# ce3_redraw.net
KiCad netlist of a schematic drawn in EAGLE
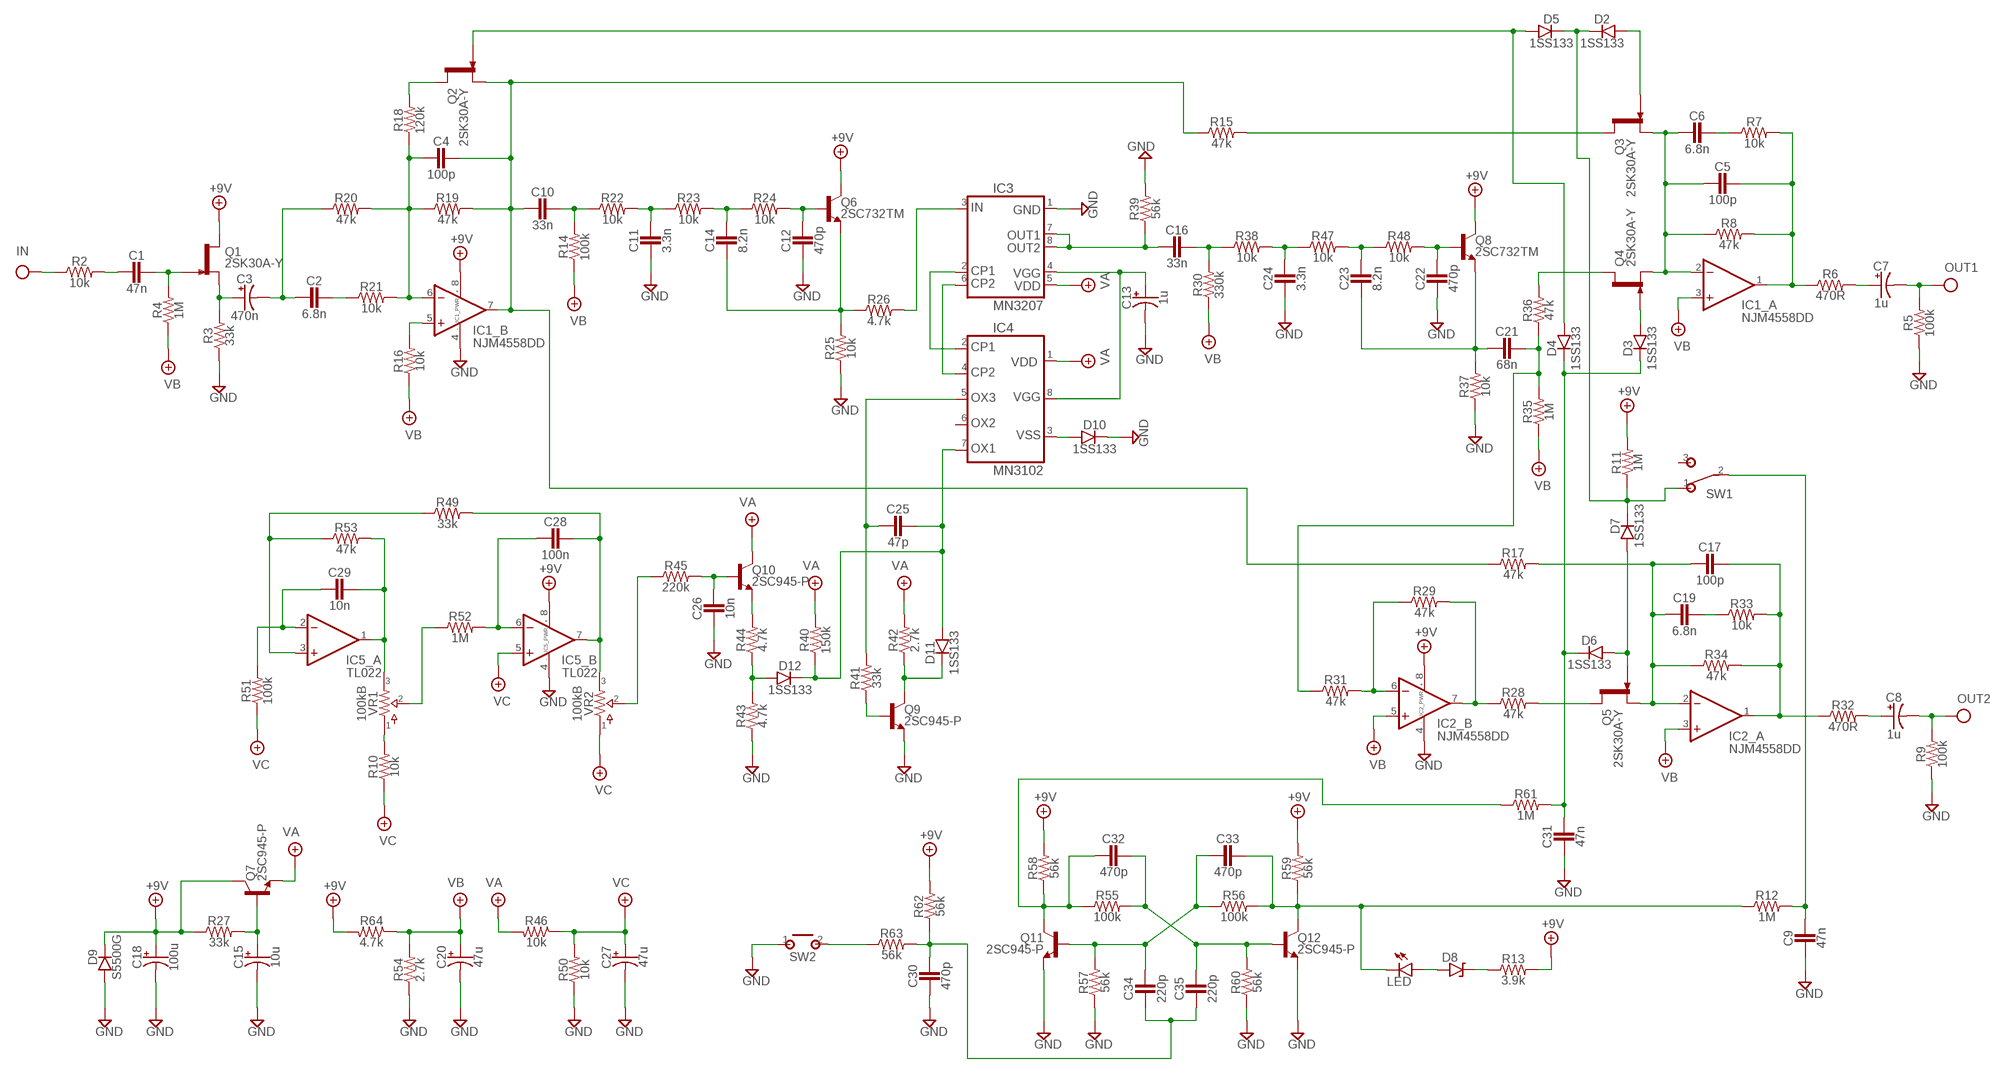
[diagram p0: schematic, sheet 1]

(export (version "E")
  (design (tool "Eeschema 10.0.6"))
  (components
    (comp (ref "C1")
      (value "47n")
      (footprint "eagle-import:BOX_SMALL")
      (libsource (lib "eagle-import") (part "CER/FILMBOX.1"))
    )
    (comp (ref "C2")
      (value "6.8n")
      (footprint "eagle-import:BOX_SMALL")
      (libsource (lib "eagle-import") (part "CER/FILMBOX.1"))
    )
    (comp (ref "C3")
      (value "470n")
      (footprint "eagle-import:040_020")
      (libsource (lib "eagle-import") (part "0400"))
    )
    (comp (ref "C4")
      (value "100p")
      (footprint "eagle-import:BOX_SMALL")
      (libsource (lib "eagle-import") (part "CER/FILMBOX.1"))
    )
    (comp (ref "C5")
      (value "100p")
      (footprint "eagle-import:BOX_SMALL")
      (libsource (lib "eagle-import") (part "CER/FILMBOX.1"))
    )
    (comp (ref "C6")
      (value "6.8n")
      (footprint "eagle-import:BOX_SMALL")
      (libsource (lib "eagle-import") (part "CER/FILMBOX.1"))
    )
    (comp (ref "C7")
      (value "1u")
      (footprint "eagle-import:040_020")
      (libsource (lib "eagle-import") (part "0400"))
    )
    (comp (ref "C8")
      (value "1u")
      (footprint "eagle-import:040_020")
      (libsource (lib "eagle-import") (part "0400"))
    )
    (comp (ref "C9")
      (value "47n")
      (footprint "eagle-import:BOX_SMALL")
      (libsource (lib "eagle-import") (part "CER/FILMBOX.1"))
    )
    (comp (ref "C10")
      (value "33n")
      (footprint "eagle-import:BOX_SMALL")
      (libsource (lib "eagle-import") (part "CER/FILMBOX.1"))
    )
    (comp (ref "C11")
      (value "3.3n")
      (footprint "eagle-import:BOX_SMALL")
      (libsource (lib "eagle-import") (part "CER/FILMBOX.1"))
    )
    (comp (ref "C12")
      (value "470p")
      (footprint "eagle-import:BOX_SMALL")
      (libsource (lib "eagle-import") (part "CER/FILMBOX.1"))
    )
    (comp (ref "C13")
      (value "1u")
      (footprint "eagle-import:040_020")
      (libsource (lib "eagle-import") (part "0400"))
    )
    (comp (ref "C14")
      (value "8.2n")
      (footprint "eagle-import:BOX_SMALL")
      (libsource (lib "eagle-import") (part "CER/FILMBOX.1"))
    )
    (comp (ref "C15")
      (value "10u")
      (footprint "eagle-import:040_020")
      (libsource (lib "eagle-import") (part "0400"))
    )
    (comp (ref "C16")
      (value "33n")
      (footprint "eagle-import:BOX_SMALL")
      (libsource (lib "eagle-import") (part "CER/FILMBOX.1"))
    )
    (comp (ref "C17")
      (value "100p")
      (footprint "eagle-import:BOX_SMALL")
      (libsource (lib "eagle-import") (part "CER/FILMBOX.1"))
    )
    (comp (ref "C18")
      (value "100u")
      (footprint "eagle-import:040_020")
      (libsource (lib "eagle-import") (part "0400"))
    )
    (comp (ref "C19")
      (value "6.8n")
      (footprint "eagle-import:BOX_SMALL")
      (libsource (lib "eagle-import") (part "CER/FILMBOX.1"))
    )
    (comp (ref "C20")
      (value "47u")
      (footprint "eagle-import:040_020")
      (libsource (lib "eagle-import") (part "0400"))
    )
    (comp (ref "C21")
      (value "68n")
      (footprint "eagle-import:BOX_SMALL")
      (libsource (lib "eagle-import") (part "CER/FILMBOX.1"))
    )
    (comp (ref "C22")
      (value "470p")
      (footprint "eagle-import:BOX_SMALL")
      (libsource (lib "eagle-import") (part "CER/FILMBOX.1"))
    )
    (comp (ref "C23")
      (value "8.2n")
      (footprint "eagle-import:BOX_SMALL")
      (libsource (lib "eagle-import") (part "CER/FILMBOX.1"))
    )
    (comp (ref "C24")
      (value "3.3n")
      (footprint "eagle-import:BOX_SMALL")
      (libsource (lib "eagle-import") (part "CER/FILMBOX.1"))
    )
    (comp (ref "C25")
      (value "47p")
      (footprint "eagle-import:BOX_SMALL")
      (libsource (lib "eagle-import") (part "CER/FILMBOX.1"))
    )
    (comp (ref "C26")
      (value "10n")
      (footprint "eagle-import:BOX_SMALL")
      (libsource (lib "eagle-import") (part "CER/FILMBOX.1"))
    )
    (comp (ref "C27")
      (value "47u")
      (footprint "eagle-import:040_020")
      (libsource (lib "eagle-import") (part "0400"))
    )
    (comp (ref "C28")
      (value "100n")
      (footprint "eagle-import:BOX_SMALL")
      (libsource (lib "eagle-import") (part "CER/FILMBOX.1"))
    )
    (comp (ref "C29")
      (value "10n")
      (footprint "eagle-import:BOX_SMALL")
      (libsource (lib "eagle-import") (part "CER/FILMBOX.1"))
    )
    (comp (ref "C30")
      (value "470p")
      (footprint "eagle-import:BOX_SMALL")
      (libsource (lib "eagle-import") (part "CER/FILMBOX.1"))
    )
    (comp (ref "C31")
      (value "47n")
      (footprint "eagle-import:BOX_SMALL")
      (libsource (lib "eagle-import") (part "CER/FILMBOX.1"))
    )
    (comp (ref "C32")
      (value "470p")
      (footprint "eagle-import:BOX_SMALL")
      (libsource (lib "eagle-import") (part "CER/FILMBOX.1"))
    )
    (comp (ref "C33")
      (value "470p")
      (footprint "eagle-import:BOX_SMALL")
      (libsource (lib "eagle-import") (part "CER/FILMBOX.1"))
    )
    (comp (ref "C34")
      (value "220p")
      (footprint "eagle-import:BOX_SMALL")
      (libsource (lib "eagle-import") (part "CER/FILMBOX.1"))
    )
    (comp (ref "C35")
      (value "220p")
      (footprint "eagle-import:BOX_SMALL")
      (libsource (lib "eagle-import") (part "CER/FILMBOX.1"))
    )
    (comp (ref "D2")
      (value "1SS133")
      (footprint "eagle-import:DO35-2")
      (libsource (lib "eagle-import") (part "DO35.2"))
    )
    (comp (ref "D3")
      (value "1SS133")
      (footprint "eagle-import:DO35-2")
      (libsource (lib "eagle-import") (part "DO35.2"))
    )
    (comp (ref "D4")
      (value "1SS133")
      (footprint "eagle-import:DO35-2")
      (libsource (lib "eagle-import") (part "DO35.2"))
    )
    (comp (ref "D5")
      (value "1SS133")
      (footprint "eagle-import:DO35-2")
      (libsource (lib "eagle-import") (part "DO35.2"))
    )
    (comp (ref "D6")
      (value "1SS133")
      (footprint "eagle-import:DO35-2")
      (libsource (lib "eagle-import") (part "DO35.2"))
    )
    (comp (ref "D7")
      (value "1SS133")
      (footprint "eagle-import:DO35-2")
      (libsource (lib "eagle-import") (part "DO35.2"))
    )
    (comp (ref "D8")
      (value "ZENER.2")
      (footprint "eagle-import:DO41-2")
      (libsource (lib "eagle-import") (part "ZENER.2"))
    )
    (comp (ref "D9")
      (value "S5500G")
      (footprint "eagle-import:DO35-2")
      (libsource (lib "eagle-import") (part "DO35.2"))
    )
    (comp (ref "D10")
      (value "1SS133")
      (footprint "eagle-import:DO35-2")
      (libsource (lib "eagle-import") (part "DO35.2"))
    )
    (comp (ref "D11")
      (value "1SS133")
      (footprint "eagle-import:DO35-2")
      (libsource (lib "eagle-import") (part "DO35.2"))
    )
    (comp (ref "D12")
      (value "1SS133")
      (footprint "eagle-import:DO35-2")
      (libsource (lib "eagle-import") (part "DO35.2"))
    )
    (comp (ref "IC1")
      (value "NJM4558DD")
      (footprint "eagle-import:DIL0")
      (libsource (lib "eagle-import") (part "DUALTH"))
    )
    (comp (ref "IC2")
      (value "NJM4558DD")
      (footprint "eagle-import:DIL0")
      (libsource (lib "eagle-import") (part "DUALTH"))
    )
    (comp (ref "IC3")
      (value "MN3207")
      (footprint "eagle-import:DIL0")
      (libsource (lib "eagle-import") (part "BL3208"))
    )
    (comp (ref "IC4")
      (value "MN3102")
      (footprint "eagle-import:DIL8")
      (libsource (lib "eagle-import") (part "CLOCK"))
    )
    (comp (ref "IC5")
      (value "TL022")
      (footprint "eagle-import:DIL0")
      (libsource (lib "eagle-import") (part "DUALTH"))
    )
    (comp (ref "LED")
      (value "LED")
      (footprint "eagle-import:3MM_D")
      (libsource (lib "eagle-import") (part "LED"))
    )
    (comp (ref "Q1")
      (value "2SK30A-Y")
      (footprint "eagle-import:TO92-")
      (libsource (lib "eagle-import") (part "2N5457"))
    )
    (comp (ref "Q2")
      (value "2SK30A-Y")
      (footprint "eagle-import:TO92-")
      (libsource (lib "eagle-import") (part "2N5457"))
    )
    (comp (ref "Q3")
      (value "2SK30A-Y")
      (footprint "eagle-import:TO92-")
      (libsource (lib "eagle-import") (part "2N5457"))
    )
    (comp (ref "Q4")
      (value "2SK30A-Y")
      (footprint "eagle-import:TO92-")
      (libsource (lib "eagle-import") (part "2N5457"))
    )
    (comp (ref "Q5")
      (value "2SK30A-Y")
      (footprint "eagle-import:TO92-")
      (libsource (lib "eagle-import") (part "2N5457"))
    )
    (comp (ref "Q6")
      (value "2SC732TM")
      (footprint "eagle-import:TO92-")
      (libsource (lib "eagle-import") (part "2SC828A"))
    )
    (comp (ref "Q7")
      (value "2SC945-P")
      (footprint "eagle-import:TO92-")
      (libsource (lib "eagle-import") (part "2SC828A"))
    )
    (comp (ref "Q8")
      (value "2SC732TM")
      (footprint "eagle-import:TO92-")
      (libsource (lib "eagle-import") (part "2SC828A"))
    )
    (comp (ref "Q9")
      (value "2SC945-P")
      (footprint "eagle-import:TO92-")
      (libsource (lib "eagle-import") (part "2SC828A"))
    )
    (comp (ref "Q10")
      (value "2SC945-P")
      (footprint "eagle-import:TO92-")
      (libsource (lib "eagle-import") (part "2SC828A"))
    )
    (comp (ref "Q11")
      (value "2SC945-P")
      (footprint "eagle-import:TO92-")
      (libsource (lib "eagle-import") (part "2SC828A"))
    )
    (comp (ref "Q12")
      (value "2SC945-P")
      (footprint "eagle-import:TO92-")
      (libsource (lib "eagle-import") (part "2SC828A"))
    )
    (comp (ref "R2")
      (value "10k")
      (footprint "eagle-import:R0207_3")
      (libsource (lib "eagle-import") (part "R_.3B"))
    )
    (comp (ref "R3")
      (value "33k")
      (footprint "eagle-import:R0207_3")
      (libsource (lib "eagle-import") (part "R_.3B"))
    )
    (comp (ref "R4")
      (value "1M")
      (footprint "eagle-import:R0207_3")
      (libsource (lib "eagle-import") (part "R_.3B"))
    )
    (comp (ref "R5")
      (value "100k")
      (footprint "eagle-import:R0207_3")
      (libsource (lib "eagle-import") (part "R_.3B"))
    )
    (comp (ref "R6")
      (value "470R")
      (footprint "eagle-import:R0207_3")
      (libsource (lib "eagle-import") (part "R_.3B"))
    )
    (comp (ref "R7")
      (value "10k")
      (footprint "eagle-import:R0207_3")
      (libsource (lib "eagle-import") (part "R_.3B"))
    )
    (comp (ref "R8")
      (value "47k")
      (footprint "eagle-import:R0207_3")
      (libsource (lib "eagle-import") (part "R_.3B"))
    )
    (comp (ref "R9")
      (value "100k")
      (footprint "eagle-import:R0207_3")
      (libsource (lib "eagle-import") (part "R_.3B"))
    )
    (comp (ref "R10")
      (value "10k")
      (footprint "eagle-import:R0207_3")
      (libsource (lib "eagle-import") (part "R_.3B"))
    )
    (comp (ref "R11")
      (value "1M")
      (footprint "eagle-import:R0207_3")
      (libsource (lib "eagle-import") (part "R_.3B"))
    )
    (comp (ref "R12")
      (value "1M")
      (footprint "eagle-import:R0207_3")
      (libsource (lib "eagle-import") (part "R_.3B"))
    )
    (comp (ref "R13")
      (value "3.9k")
      (footprint "eagle-import:R0207_3")
      (libsource (lib "eagle-import") (part "R_.3B"))
    )
    (comp (ref "R14")
      (value "100k")
      (footprint "eagle-import:R0207_3")
      (libsource (lib "eagle-import") (part "R_.3B"))
    )
    (comp (ref "R15")
      (value "47k")
      (footprint "eagle-import:R0207_3")
      (libsource (lib "eagle-import") (part "R_.3B"))
    )
    (comp (ref "R16")
      (value "10k")
      (footprint "eagle-import:R0207_3")
      (libsource (lib "eagle-import") (part "R_.3B"))
    )
    (comp (ref "R17")
      (value "47k")
      (footprint "eagle-import:R0207_3")
      (libsource (lib "eagle-import") (part "R_.3B"))
    )
    (comp (ref "R18")
      (value "120k")
      (footprint "eagle-import:R0207_3")
      (libsource (lib "eagle-import") (part "R_.3B"))
    )
    (comp (ref "R19")
      (value "47k")
      (footprint "eagle-import:R0207_3")
      (libsource (lib "eagle-import") (part "R_.3B"))
    )
    (comp (ref "R20")
      (value "47k")
      (footprint "eagle-import:R0207_3")
      (libsource (lib "eagle-import") (part "R_.3B"))
    )
    (comp (ref "R21")
      (value "10k")
      (footprint "eagle-import:R0207_3")
      (libsource (lib "eagle-import") (part "R_.3B"))
    )
    (comp (ref "R22")
      (value "10k")
      (footprint "eagle-import:R0207_3")
      (libsource (lib "eagle-import") (part "R_.3B"))
    )
    (comp (ref "R23")
      (value "10k")
      (footprint "eagle-import:R0207_3")
      (libsource (lib "eagle-import") (part "R_.3B"))
    )
    (comp (ref "R24")
      (value "10k")
      (footprint "eagle-import:R0207_3")
      (libsource (lib "eagle-import") (part "R_.3B"))
    )
    (comp (ref "R25")
      (value "10k")
      (footprint "eagle-import:R0207_3")
      (libsource (lib "eagle-import") (part "R_.3B"))
    )
    (comp (ref "R26")
      (value "4.7k")
      (footprint "eagle-import:R0207_3")
      (libsource (lib "eagle-import") (part "R_.3B"))
    )
    (comp (ref "R27")
      (value "33k")
      (footprint "eagle-import:R0207_3")
      (libsource (lib "eagle-import") (part "R_.3B"))
    )
    (comp (ref "R28")
      (value "47k")
      (footprint "eagle-import:R0207_3")
      (libsource (lib "eagle-import") (part "R_.3B"))
    )
    (comp (ref "R29")
      (value "47k")
      (footprint "eagle-import:R0207_3")
      (libsource (lib "eagle-import") (part "R_.3B"))
    )
    (comp (ref "R30")
      (value "330k")
      (footprint "eagle-import:R0207_3")
      (libsource (lib "eagle-import") (part "R_.3B"))
    )
    (comp (ref "R31")
      (value "47k")
      (footprint "eagle-import:R0207_3")
      (libsource (lib "eagle-import") (part "R_.3B"))
    )
    (comp (ref "R32")
      (value "470R")
      (footprint "eagle-import:R0207_3")
      (libsource (lib "eagle-import") (part "R_.3B"))
    )
    (comp (ref "R33")
      (value "10k")
      (footprint "eagle-import:R0207_3")
      (libsource (lib "eagle-import") (part "R_.3B"))
    )
    (comp (ref "R34")
      (value "47k")
      (footprint "eagle-import:R0207_3")
      (libsource (lib "eagle-import") (part "R_.3B"))
    )
    (comp (ref "R35")
      (value "1M")
      (footprint "eagle-import:R0207_3")
      (libsource (lib "eagle-import") (part "R_.3B"))
    )
    (comp (ref "R36")
      (value "47k")
      (footprint "eagle-import:R0207_3")
      (libsource (lib "eagle-import") (part "R_.3B"))
    )
    (comp (ref "R37")
      (value "10k")
      (footprint "eagle-import:R0207_3")
      (libsource (lib "eagle-import") (part "R_.3B"))
    )
    (comp (ref "R38")
      (value "10k")
      (footprint "eagle-import:R0207_3")
      (libsource (lib "eagle-import") (part "R_.3B"))
    )
    (comp (ref "R39")
      (value "56k")
      (footprint "eagle-import:R0207_3")
      (libsource (lib "eagle-import") (part "R_.3B"))
    )
    (comp (ref "R40")
      (value "150k")
      (footprint "eagle-import:R0207_3")
      (libsource (lib "eagle-import") (part "R_.3B"))
    )
    (comp (ref "R41")
      (value "33k")
      (footprint "eagle-import:R0207_3")
      (libsource (lib "eagle-import") (part "R_.3B"))
    )
    (comp (ref "R42")
      (value "2.7k")
      (footprint "eagle-import:R0207_3")
      (libsource (lib "eagle-import") (part "R_.3B"))
    )
    (comp (ref "R43")
      (value "4.7k")
      (footprint "eagle-import:R0207_3")
      (libsource (lib "eagle-import") (part "R_.3B"))
    )
    (comp (ref "R44")
      (value "4.7k")
      (footprint "eagle-import:R0207_3")
      (libsource (lib "eagle-import") (part "R_.3B"))
    )
    (comp (ref "R45")
      (value "220k")
      (footprint "eagle-import:R0207_3")
      (libsource (lib "eagle-import") (part "R_.3B"))
    )
    (comp (ref "R46")
      (value "10k")
      (footprint "eagle-import:R0207_3")
      (libsource (lib "eagle-import") (part "R_.3B"))
    )
    (comp (ref "R47")
      (value "10k")
      (footprint "eagle-import:R0207_3")
      (libsource (lib "eagle-import") (part "R_.3B"))
    )
    (comp (ref "R48")
      (value "10k")
      (footprint "eagle-import:R0207_3")
      (libsource (lib "eagle-import") (part "R_.3B"))
    )
    (comp (ref "R49")
      (value "33k")
      (footprint "eagle-import:R0207_3")
      (libsource (lib "eagle-import") (part "R_.3B"))
    )
    (comp (ref "R50")
      (value "10k")
      (footprint "eagle-import:R0207_3")
      (libsource (lib "eagle-import") (part "R_.3B"))
    )
    (comp (ref "R51")
      (value "100k")
      (footprint "eagle-import:R0207_3")
      (libsource (lib "eagle-import") (part "R_.3B"))
    )
    (comp (ref "R52")
      (value "1M")
      (footprint "eagle-import:R0207_3")
      (libsource (lib "eagle-import") (part "R_.3B"))
    )
    (comp (ref "R53")
      (value "47k")
      (footprint "eagle-import:R0207_3")
      (libsource (lib "eagle-import") (part "R_.3B"))
    )
    (comp (ref "R54")
      (value "2.7k")
      (footprint "eagle-import:R0207_3")
      (libsource (lib "eagle-import") (part "R_.3B"))
    )
    (comp (ref "R55")
      (value "100k")
      (footprint "eagle-import:R0207_3")
      (libsource (lib "eagle-import") (part "R_.3B"))
    )
    (comp (ref "R56")
      (value "100k")
      (footprint "eagle-import:R0207_3")
      (libsource (lib "eagle-import") (part "R_.3B"))
    )
    (comp (ref "R57")
      (value "56k")
      (footprint "eagle-import:R0207_3")
      (libsource (lib "eagle-import") (part "R_.3B"))
    )
    (comp (ref "R58")
      (value "56k")
      (footprint "eagle-import:R0207_3")
      (libsource (lib "eagle-import") (part "R_.3B"))
    )
    (comp (ref "R59")
      (value "56k")
      (footprint "eagle-import:R0207_3")
      (libsource (lib "eagle-import") (part "R_.3B"))
    )
    (comp (ref "R60")
      (value "56k")
      (footprint "eagle-import:R0207_3")
      (libsource (lib "eagle-import") (part "R_.3B"))
    )
    (comp (ref "R61")
      (value "1M")
      (footprint "eagle-import:R0207_3")
      (libsource (lib "eagle-import") (part "R_.3B"))
    )
    (comp (ref "R62")
      (value "56k")
      (footprint "eagle-import:R0207_3")
      (libsource (lib "eagle-import") (part "R_.3B"))
    )
    (comp (ref "R63")
      (value "56k")
      (footprint "eagle-import:R0207_3")
      (libsource (lib "eagle-import") (part "R_.3B"))
    )
    (comp (ref "R64")
      (value "4.7k")
      (footprint "eagle-import:R0207_3")
      (libsource (lib "eagle-import") (part "R_.3B"))
    )
    (comp (ref "SW1")
      (value "SPDT")
      (footprint "eagle-import:M9040P")
      (libsource (lib "eagle-import") (part "SPDT"))
    )
    (comp (ref "SW2")
      (value "MOMENTARY")
      (footprint "eagle-import:SPST")
      (libsource (lib "eagle-import") (part "MOMENTARY"))
    )
    (comp (ref "VR1")
      (value "100kB")
      (footprint "eagle-import:16MM")
      (libsource (lib "eagle-import") (part "POTS16MM"))
    )
    (comp (ref "VR2")
      (value "100kB")
      (footprint "eagle-import:16MM")
      (libsource (lib "eagle-import") (part "POTS16MM"))
    )
  )
  (nets
    (net (code "1") (name "+9V") (class "Default")
      (node (ref "C18") (pin "+") (pinfunction "+_+") (pintype "passive"))
      (node (ref "D9") (pin "C") (pinfunction "C_C") (pintype "passive"))
      (node (ref "IC1") (pin "8") (pinfunction "V+_8") (pintype "power_in"))
      (node (ref "IC2") (pin "8") (pinfunction "V+_8") (pintype "power_in"))
      (node (ref "IC5") (pin "8") (pinfunction "V+_8") (pintype "power_in"))
      (node (ref "Q1") (pin "3") (pinfunction "D_3") (pintype "passive"))
      (node (ref "Q6") (pin "2") (pinfunction "C_2") (pintype "passive"))
      (node (ref "Q7") (pin "2") (pinfunction "C_2") (pintype "passive"))
      (node (ref "Q8") (pin "2") (pinfunction "C_2") (pintype "passive"))
      (node (ref "R11") (pin "2") (pinfunction "2_2") (pintype "passive"))
      (node (ref "R13") (pin "2") (pinfunction "2_2") (pintype "passive"))
      (node (ref "R27") (pin "1") (pinfunction "1_1") (pintype "passive"))
      (node (ref "R58") (pin "2") (pinfunction "2_2") (pintype "passive"))
      (node (ref "R59") (pin "2") (pinfunction "2_2") (pintype "passive"))
      (node (ref "R62") (pin "2") (pinfunction "2_2") (pintype "passive"))
      (node (ref "R64") (pin "2") (pinfunction "2_2") (pintype "passive"))
    )
    (net (code "2") (name "GND") (class "Default")
      (node (ref "C11") (pin "2") (pinfunction "2_2") (pintype "passive"))
      (node (ref "C12") (pin "2") (pinfunction "2_2") (pintype "passive"))
      (node (ref "C13") (pin "-") (pinfunction "-_-") (pintype "passive"))
      (node (ref "C15") (pin "-") (pinfunction "-_-") (pintype "passive"))
      (node (ref "C18") (pin "-") (pinfunction "-_-") (pintype "passive"))
      (node (ref "C20") (pin "-") (pinfunction "-_-") (pintype "passive"))
      (node (ref "C22") (pin "2") (pinfunction "2_2") (pintype "passive"))
      (node (ref "C24") (pin "2") (pinfunction "2_2") (pintype "passive"))
      (node (ref "C26") (pin "2") (pinfunction "2_2") (pintype "passive"))
      (node (ref "C27") (pin "-") (pinfunction "-_-") (pintype "passive"))
      (node (ref "C30") (pin "2") (pinfunction "2_2") (pintype "passive"))
      (node (ref "C31") (pin "2") (pinfunction "2_2") (pintype "passive"))
      (node (ref "C9") (pin "2") (pinfunction "2_2") (pintype "passive"))
      (node (ref "D10") (pin "C") (pinfunction "C_C") (pintype "passive"))
      (node (ref "D9") (pin "A") (pinfunction "A_A") (pintype "passive"))
      (node (ref "IC1") (pin "4") (pinfunction "V-_4") (pintype "power_in"))
      (node (ref "IC2") (pin "4") (pinfunction "V-_4") (pintype "power_in"))
      (node (ref "IC3") (pin "1") (pinfunction "1_1") (pintype "bidirectional"))
      (node (ref "IC5") (pin "4") (pinfunction "V-_4") (pintype "power_in"))
      (node (ref "Q11") (pin "3") (pinfunction "E_3") (pintype "passive"))
      (node (ref "Q12") (pin "3") (pinfunction "E_3") (pintype "passive"))
      (node (ref "Q9") (pin "3") (pinfunction "E_3") (pintype "passive"))
      (node (ref "R25") (pin "1") (pinfunction "1_1") (pintype "passive"))
      (node (ref "R3") (pin "1") (pinfunction "1_1") (pintype "passive"))
      (node (ref "R37") (pin "1") (pinfunction "1_1") (pintype "passive"))
      (node (ref "R39") (pin "2") (pinfunction "2_2") (pintype "passive"))
      (node (ref "R43") (pin "1") (pinfunction "1_1") (pintype "passive"))
      (node (ref "R5") (pin "1") (pinfunction "1_1") (pintype "passive"))
      (node (ref "R50") (pin "1") (pinfunction "1_1") (pintype "passive"))
      (node (ref "R54") (pin "1") (pinfunction "1_1") (pintype "passive"))
      (node (ref "R57") (pin "1") (pinfunction "1_1") (pintype "passive"))
      (node (ref "R60") (pin "1") (pinfunction "1_1") (pintype "passive"))
      (node (ref "R9") (pin "1") (pinfunction "1_1") (pintype "passive"))
      (node (ref "SW2") (pin "1") (pinfunction "P_1") (pintype "passive"))
    )
    (net (code "3") (name "IN") (class "Default")
      (node (ref "R2") (pin "1") (pinfunction "1_1") (pintype "passive"))
    )
    (net (code "4") (name "Net-(C1-Pad2)") (class "Default")
      (node (ref "C1") (pin "2") (pinfunction "2_2") (pintype "passive"))
      (node (ref "R2") (pin "2") (pinfunction "2_2") (pintype "passive"))
    )
    (net (code "5") (name "Net-(C2-Pad1)") (class "Default")
      (node (ref "C2") (pin "1") (pinfunction "1_1") (pintype "passive"))
      (node (ref "R21") (pin "1") (pinfunction "1_1") (pintype "passive"))
    )
    (net (code "6") (name "Net-(C2-Pad2)") (class "Default")
      (node (ref "C2") (pin "2") (pinfunction "2_2") (pintype "passive"))
      (node (ref "C3") (pin "-") (pinfunction "-_-") (pintype "passive"))
      (node (ref "R20") (pin "1") (pinfunction "1_1") (pintype "passive"))
    )
    (net (code "7") (name "Net-(C6-Pad1)") (class "Default")
      (node (ref "C6") (pin "1") (pinfunction "1_1") (pintype "passive"))
      (node (ref "R7") (pin "1") (pinfunction "1_1") (pintype "passive"))
    )
    (net (code "8") (name "Net-(C7-Pad+)") (class "Default")
      (node (ref "C7") (pin "+") (pinfunction "+_+") (pintype "passive"))
      (node (ref "R6") (pin "2") (pinfunction "2_2") (pintype "passive"))
    )
    (net (code "9") (name "Net-(C8-Pad+)") (class "Default")
      (node (ref "C8") (pin "+") (pinfunction "+_+") (pintype "passive"))
      (node (ref "R32") (pin "2") (pinfunction "2_2") (pintype "passive"))
    )
    (net (code "10") (name "Net-(C10-Pad1)") (class "Default")
      (node (ref "C10") (pin "1") (pinfunction "1_1") (pintype "passive"))
      (node (ref "R14") (pin "2") (pinfunction "2_2") (pintype "passive"))
      (node (ref "R22") (pin "1") (pinfunction "1_1") (pintype "passive"))
    )
    (net (code "11") (name "Net-(C11-Pad1)") (class "Default")
      (node (ref "C11") (pin "1") (pinfunction "1_1") (pintype "passive"))
      (node (ref "R22") (pin "2") (pinfunction "2_2") (pintype "passive"))
      (node (ref "R23") (pin "1") (pinfunction "1_1") (pintype "passive"))
    )
    (net (code "12") (name "Net-(C14-Pad1)") (class "Default")
      (node (ref "C14") (pin "1") (pinfunction "1_1") (pintype "passive"))
      (node (ref "R23") (pin "2") (pinfunction "2_2") (pintype "passive"))
      (node (ref "R24") (pin "1") (pinfunction "1_1") (pintype "passive"))
    )
    (net (code "13") (name "Net-(C16-Pad1)") (class "Default")
      (node (ref "C16") (pin "1") (pinfunction "1_1") (pintype "passive"))
      (node (ref "R30") (pin "2") (pinfunction "2_2") (pintype "passive"))
      (node (ref "R38") (pin "1") (pinfunction "1_1") (pintype "passive"))
    )
    (net (code "14") (name "Net-(C16-Pad2)") (class "Default")
      (node (ref "C16") (pin "2") (pinfunction "2_2") (pintype "passive"))
      (node (ref "IC3") (pin "7") (pinfunction "7_7") (pintype "bidirectional"))
      (node (ref "IC3") (pin "8") (pinfunction "8_8") (pintype "bidirectional"))
      (node (ref "R39") (pin "1") (pinfunction "1_1") (pintype "passive"))
    )
    (net (code "15") (name "Net-(C19-Pad1)") (class "Default")
      (node (ref "C19") (pin "1") (pinfunction "1_1") (pintype "passive"))
      (node (ref "R33") (pin "1") (pinfunction "1_1") (pintype "passive"))
    )
    (net (code "16") (name "Net-(C21-Pad1)") (class "Default")
      (node (ref "C21") (pin "1") (pinfunction "1_1") (pintype "passive"))
      (node (ref "R31") (pin "1") (pinfunction "1_1") (pintype "passive"))
      (node (ref "R35") (pin "2") (pinfunction "2_2") (pintype "passive"))
      (node (ref "R36") (pin "1") (pinfunction "1_1") (pintype "passive"))
    )
    (net (code "17") (name "Net-(C23-Pad1)") (class "Default")
      (node (ref "C23") (pin "1") (pinfunction "1_1") (pintype "passive"))
      (node (ref "R47") (pin "2") (pinfunction "2_2") (pintype "passive"))
      (node (ref "R48") (pin "1") (pinfunction "1_1") (pintype "passive"))
    )
    (net (code "18") (name "Net-(C24-Pad1)") (class "Default")
      (node (ref "C24") (pin "1") (pinfunction "1_1") (pintype "passive"))
      (node (ref "R38") (pin "2") (pinfunction "2_2") (pintype "passive"))
      (node (ref "R47") (pin "1") (pinfunction "1_1") (pintype "passive"))
    )
    (net (code "19") (name "Net-(C30-Pad1)") (class "Default")
      (node (ref "C30") (pin "1") (pinfunction "1_1") (pintype "passive"))
      (node (ref "C34") (pin "2") (pinfunction "2_2") (pintype "passive"))
      (node (ref "C35") (pin "2") (pinfunction "2_2") (pintype "passive"))
      (node (ref "R62") (pin "1") (pinfunction "1_1") (pintype "passive"))
      (node (ref "R63") (pin "2") (pinfunction "2_2") (pintype "passive"))
    )
    (net (code "20") (name "Net-(C31-Pad1)") (class "Default")
      (node (ref "C31") (pin "1") (pinfunction "1_1") (pintype "passive"))
      (node (ref "D3") (pin "C") (pinfunction "C_C") (pintype "passive"))
      (node (ref "D4") (pin "C") (pinfunction "C_C") (pintype "passive"))
      (node (ref "D6") (pin "C") (pinfunction "C_C") (pintype "passive"))
      (node (ref "R61") (pin "2") (pinfunction "2_2") (pintype "passive"))
    )
    (net (code "21") (name "Net-(D8-PadC)") (class "Default")
      (node (ref "D8") (pin "C") (pinfunction "C_C") (pintype "passive"))
      (node (ref "R13") (pin "1") (pinfunction "1_1") (pintype "passive"))
    )
    (net (code "22") (name "Net-(D12-PadA)") (class "Default")
      (node (ref "D12") (pin "A") (pinfunction "A_A") (pintype "passive"))
      (node (ref "R43") (pin "2") (pinfunction "2_2") (pintype "passive"))
      (node (ref "R44") (pin "1") (pinfunction "1_1") (pintype "passive"))
    )
    (net (code "23") (name "Net-(IC1A--IN)") (class "Default")
      (node (ref "C5") (pin "2") (pinfunction "2_2") (pintype "passive"))
      (node (ref "C6") (pin "2") (pinfunction "2_2") (pintype "passive"))
      (node (ref "IC1") (pin "2") (pinfunction "-IN_2") (pintype "input"))
      (node (ref "Q3") (pin "2") (pinfunction "S_2") (pintype "passive"))
      (node (ref "Q4") (pin "2") (pinfunction "S_2") (pintype "passive"))
      (node (ref "R8") (pin "1") (pinfunction "1_1") (pintype "passive"))
    )
    (net (code "24") (name "Net-(IC1A-OUT)") (class "Default")
      (node (ref "C5") (pin "1") (pinfunction "1_1") (pintype "passive"))
      (node (ref "IC1") (pin "1") (pinfunction "OUT_1") (pintype "output"))
      (node (ref "R6") (pin "1") (pinfunction "1_1") (pintype "passive"))
      (node (ref "R7") (pin "2") (pinfunction "2_2") (pintype "passive"))
      (node (ref "R8") (pin "2") (pinfunction "2_2") (pintype "passive"))
    )
    (net (code "25") (name "Net-(IC1B-+IN)") (class "Default")
      (node (ref "IC1") (pin "5") (pinfunction "+IN_5") (pintype "input"))
      (node (ref "R16") (pin "2") (pinfunction "2_2") (pintype "passive"))
    )
    (net (code "26") (name "Net-(IC1B--IN)") (class "Default")
      (node (ref "C4") (pin "2") (pinfunction "2_2") (pintype "passive"))
      (node (ref "IC1") (pin "6") (pinfunction "-IN_6") (pintype "input"))
      (node (ref "R18") (pin "1") (pinfunction "1_1") (pintype "passive"))
      (node (ref "R19") (pin "1") (pinfunction "1_1") (pintype "passive"))
      (node (ref "R20") (pin "2") (pinfunction "2_2") (pintype "passive"))
      (node (ref "R21") (pin "2") (pinfunction "2_2") (pintype "passive"))
    )
    (net (code "27") (name "Net-(IC1B-OUT)") (class "Default")
      (node (ref "C10") (pin "2") (pinfunction "2_2") (pintype "passive"))
      (node (ref "C4") (pin "1") (pinfunction "1_1") (pintype "passive"))
      (node (ref "IC1") (pin "7") (pinfunction "OUT_7") (pintype "output"))
      (node (ref "Q2") (pin "2") (pinfunction "S_2") (pintype "passive"))
      (node (ref "R15") (pin "1") (pinfunction "1_1") (pintype "passive"))
      (node (ref "R17") (pin "1") (pinfunction "1_1") (pintype "passive"))
      (node (ref "R19") (pin "2") (pinfunction "2_2") (pintype "passive"))
    )
    (net (code "28") (name "Net-(IC2A--IN)") (class "Default")
      (node (ref "C17") (pin "2") (pinfunction "2_2") (pintype "passive"))
      (node (ref "C19") (pin "2") (pinfunction "2_2") (pintype "passive"))
      (node (ref "IC2") (pin "2") (pinfunction "-IN_2") (pintype "input"))
      (node (ref "Q5") (pin "2") (pinfunction "S_2") (pintype "passive"))
      (node (ref "R17") (pin "2") (pinfunction "2_2") (pintype "passive"))
      (node (ref "R34") (pin "1") (pinfunction "1_1") (pintype "passive"))
    )
    (net (code "29") (name "Net-(IC2A-OUT)") (class "Default")
      (node (ref "C17") (pin "1") (pinfunction "1_1") (pintype "passive"))
      (node (ref "IC2") (pin "1") (pinfunction "OUT_1") (pintype "output"))
      (node (ref "R32") (pin "1") (pinfunction "1_1") (pintype "passive"))
      (node (ref "R33") (pin "2") (pinfunction "2_2") (pintype "passive"))
      (node (ref "R34") (pin "2") (pinfunction "2_2") (pintype "passive"))
    )
    (net (code "30") (name "Net-(IC2B--IN)") (class "Default")
      (node (ref "IC2") (pin "6") (pinfunction "-IN_6") (pintype "input"))
      (node (ref "R29") (pin "1") (pinfunction "1_1") (pintype "passive"))
      (node (ref "R31") (pin "2") (pinfunction "2_2") (pintype "passive"))
    )
    (net (code "31") (name "Net-(IC2B-OUT)") (class "Default")
      (node (ref "IC2") (pin "7") (pinfunction "OUT_7") (pintype "output"))
      (node (ref "R28") (pin "1") (pinfunction "1_1") (pintype "passive"))
      (node (ref "R29") (pin "2") (pinfunction "2_2") (pintype "passive"))
    )
    (net (code "32") (name "Net-(IC3-Pad3)") (class "Default")
      (node (ref "IC3") (pin "3") (pinfunction "3_3") (pintype "bidirectional"))
      (node (ref "R26") (pin "2") (pinfunction "2_2") (pintype "passive"))
    )
    (net (code "33") (name "Net-(IC4-P$2)") (class "Default")
      (node (ref "IC3") (pin "2") (pinfunction "2_2") (pintype "bidirectional"))
      (node (ref "IC4") (pin "2") (pinfunction "P$2_2") (pintype "bidirectional"))
    )
    (net (code "34") (name "Net-(IC4-P$3)") (class "Default")
      (node (ref "D10") (pin "A") (pinfunction "A_A") (pintype "passive"))
      (node (ref "IC4") (pin "3") (pinfunction "P$3_3") (pintype "bidirectional"))
    )
    (net (code "35") (name "Net-(IC4-P$4)") (class "Default")
      (node (ref "IC3") (pin "6") (pinfunction "6_6") (pintype "bidirectional"))
      (node (ref "IC4") (pin "4") (pinfunction "P$4_4") (pintype "bidirectional"))
    )
    (net (code "36") (name "Net-(IC4-P$5)") (class "Default")
      (node (ref "C25") (pin "2") (pinfunction "2_2") (pintype "passive"))
      (node (ref "IC4") (pin "5") (pinfunction "P$5_5") (pintype "bidirectional"))
      (node (ref "R41") (pin "2") (pinfunction "2_2") (pintype "passive"))
    )
    (net (code "37") (name "Net-(IC4-P$7)") (class "Default")
      (node (ref "C25") (pin "1") (pinfunction "1_1") (pintype "passive"))
      (node (ref "D11") (pin "A") (pinfunction "A_A") (pintype "passive"))
      (node (ref "D12") (pin "C") (pinfunction "C_C") (pintype "passive"))
      (node (ref "IC4") (pin "7") (pinfunction "P$7_7") (pintype "bidirectional"))
      (node (ref "R40") (pin "1") (pinfunction "1_1") (pintype "passive"))
    )
    (net (code "38") (name "Net-(IC4-P$8)") (class "Default")
      (node (ref "C13") (pin "+") (pinfunction "+_+") (pintype "passive"))
      (node (ref "IC3") (pin "4") (pinfunction "4_4") (pintype "bidirectional"))
      (node (ref "IC4") (pin "8") (pinfunction "P$8_8") (pintype "bidirectional"))
    )
    (net (code "39") (name "Net-(IC5A-+IN)") (class "Default")
      (node (ref "IC5") (pin "3") (pinfunction "+IN_3") (pintype "input"))
      (node (ref "R49") (pin "1") (pinfunction "1_1") (pintype "passive"))
      (node (ref "R53") (pin "1") (pinfunction "1_1") (pintype "passive"))
    )
    (net (code "40") (name "Net-(IC5A--IN)") (class "Default")
      (node (ref "C29") (pin "2") (pinfunction "2_2") (pintype "passive"))
      (node (ref "IC5") (pin "2") (pinfunction "-IN_2") (pintype "input"))
      (node (ref "R51") (pin "2") (pinfunction "2_2") (pintype "passive"))
    )
    (net (code "41") (name "Net-(IC5A-OUT)") (class "Default")
      (node (ref "C29") (pin "1") (pinfunction "1_1") (pintype "passive"))
      (node (ref "IC5") (pin "1") (pinfunction "OUT_1") (pintype "output"))
      (node (ref "R53") (pin "2") (pinfunction "2_2") (pintype "passive"))
      (node (ref "VR1") (pin "3") (pinfunction "3_3") (pintype "passive"))
    )
    (net (code "42") (name "Net-(IC5B--IN)") (class "Default")
      (node (ref "C28") (pin "2") (pinfunction "2_2") (pintype "passive"))
      (node (ref "IC5") (pin "6") (pinfunction "-IN_6") (pintype "input"))
      (node (ref "R52") (pin "2") (pinfunction "2_2") (pintype "passive"))
    )
    (net (code "43") (name "Net-(IC5B-OUT)") (class "Default")
      (node (ref "C28") (pin "1") (pinfunction "1_1") (pintype "passive"))
      (node (ref "IC5") (pin "7") (pinfunction "OUT_7") (pintype "output"))
      (node (ref "R49") (pin "2") (pinfunction "2_2") (pintype "passive"))
      (node (ref "VR2") (pin "3") (pinfunction "3_3") (pintype "passive"))
    )
    (net (code "44") (name "Net-(LED-A)") (class "Default")
      (node (ref "D8") (pin "A") (pinfunction "A_A") (pintype "passive"))
      (node (ref "LED") (pin "ANODE") (pinfunction "A_ANODE") (pintype "passive"))
    )
    (net (code "45") (name "Net-(LED-C)") (class "Default")
      (node (ref "C33") (pin "1") (pinfunction "1_1") (pintype "passive"))
      (node (ref "LED") (pin "P$1") (pinfunction "C_P$1") (pintype "passive"))
      (node (ref "Q12") (pin "2") (pinfunction "C_2") (pintype "passive"))
      (node (ref "R12") (pin "1") (pinfunction "1_1") (pintype "passive"))
      (node (ref "R56") (pin "2") (pinfunction "2_2") (pintype "passive"))
      (node (ref "R59") (pin "1") (pinfunction "1_1") (pintype "passive"))
    )
    (net (code "46") (name "Net-(Q1-G)") (class "Default")
      (node (ref "C1") (pin "1") (pinfunction "1_1") (pintype "passive"))
      (node (ref "Q1") (pin "1") (pinfunction "G_1") (pintype "passive"))
      (node (ref "R4") (pin "2") (pinfunction "2_2") (pintype "passive"))
    )
    (net (code "47") (name "Net-(Q1-S)") (class "Default")
      (node (ref "C3") (pin "+") (pinfunction "+_+") (pintype "passive"))
      (node (ref "Q1") (pin "2") (pinfunction "S_2") (pintype "passive"))
      (node (ref "R3") (pin "2") (pinfunction "2_2") (pintype "passive"))
    )
    (net (code "48") (name "Net-(Q2-D)") (class "Default")
      (node (ref "Q2") (pin "3") (pinfunction "D_3") (pintype "passive"))
      (node (ref "R18") (pin "2") (pinfunction "2_2") (pintype "passive"))
    )
    (net (code "49") (name "Net-(Q2-G)") (class "Default")
      (node (ref "D4") (pin "A") (pinfunction "A_A") (pintype "passive"))
      (node (ref "D5") (pin "A") (pinfunction "A_A") (pintype "passive"))
      (node (ref "Q2") (pin "1") (pinfunction "G_1") (pintype "passive"))
    )
    (net (code "50") (name "Net-(Q3-D)") (class "Default")
      (node (ref "Q3") (pin "3") (pinfunction "D_3") (pintype "passive"))
      (node (ref "R15") (pin "2") (pinfunction "2_2") (pintype "passive"))
    )
    (net (code "51") (name "Net-(Q3-G)") (class "Default")
      (node (ref "D2") (pin "A") (pinfunction "A_A") (pintype "passive"))
      (node (ref "Q3") (pin "1") (pinfunction "G_1") (pintype "passive"))
    )
    (net (code "52") (name "Net-(Q4-D)") (class "Default")
      (node (ref "Q4") (pin "3") (pinfunction "D_3") (pintype "passive"))
      (node (ref "R36") (pin "2") (pinfunction "2_2") (pintype "passive"))
    )
    (net (code "53") (name "Net-(Q4-G)") (class "Default")
      (node (ref "D3") (pin "A") (pinfunction "A_A") (pintype "passive"))
      (node (ref "Q4") (pin "1") (pinfunction "G_1") (pintype "passive"))
    )
    (net (code "54") (name "Net-(Q5-D)") (class "Default")
      (node (ref "Q5") (pin "3") (pinfunction "D_3") (pintype "passive"))
      (node (ref "R28") (pin "2") (pinfunction "2_2") (pintype "passive"))
    )
    (net (code "55") (name "Net-(Q5-G)") (class "Default")
      (node (ref "D6") (pin "A") (pinfunction "A_A") (pintype "passive"))
      (node (ref "D7") (pin "A") (pinfunction "A_A") (pintype "passive"))
      (node (ref "Q5") (pin "1") (pinfunction "G_1") (pintype "passive"))
    )
    (net (code "56") (name "Net-(Q6-B)") (class "Default")
      (node (ref "C12") (pin "1") (pinfunction "1_1") (pintype "passive"))
      (node (ref "Q6") (pin "1") (pinfunction "B_1") (pintype "passive"))
      (node (ref "R24") (pin "2") (pinfunction "2_2") (pintype "passive"))
    )
    (net (code "57") (name "Net-(Q6-E)") (class "Default")
      (node (ref "C14") (pin "2") (pinfunction "2_2") (pintype "passive"))
      (node (ref "Q6") (pin "3") (pinfunction "E_3") (pintype "passive"))
      (node (ref "R25") (pin "2") (pinfunction "2_2") (pintype "passive"))
      (node (ref "R26") (pin "1") (pinfunction "1_1") (pintype "passive"))
    )
    (net (code "58") (name "Net-(Q7-B)") (class "Default")
      (node (ref "C15") (pin "+") (pinfunction "+_+") (pintype "passive"))
      (node (ref "Q7") (pin "1") (pinfunction "B_1") (pintype "passive"))
      (node (ref "R27") (pin "2") (pinfunction "2_2") (pintype "passive"))
    )
    (net (code "59") (name "Net-(Q8-B)") (class "Default")
      (node (ref "C22") (pin "1") (pinfunction "1_1") (pintype "passive"))
      (node (ref "Q8") (pin "1") (pinfunction "B_1") (pintype "passive"))
      (node (ref "R48") (pin "2") (pinfunction "2_2") (pintype "passive"))
    )
    (net (code "60") (name "Net-(Q8-E)") (class "Default")
      (node (ref "C21") (pin "2") (pinfunction "2_2") (pintype "passive"))
      (node (ref "C23") (pin "2") (pinfunction "2_2") (pintype "passive"))
      (node (ref "Q8") (pin "3") (pinfunction "E_3") (pintype "passive"))
      (node (ref "R37") (pin "2") (pinfunction "2_2") (pintype "passive"))
    )
    (net (code "61") (name "Net-(Q9-B)") (class "Default")
      (node (ref "Q9") (pin "1") (pinfunction "B_1") (pintype "passive"))
      (node (ref "R41") (pin "1") (pinfunction "1_1") (pintype "passive"))
    )
    (net (code "62") (name "Net-(Q9-C)") (class "Default")
      (node (ref "D11") (pin "C") (pinfunction "C_C") (pintype "passive"))
      (node (ref "Q9") (pin "2") (pinfunction "C_2") (pintype "passive"))
      (node (ref "R42") (pin "1") (pinfunction "1_1") (pintype "passive"))
    )
    (net (code "63") (name "Net-(Q10-B)") (class "Default")
      (node (ref "C26") (pin "1") (pinfunction "1_1") (pintype "passive"))
      (node (ref "Q10") (pin "1") (pinfunction "B_1") (pintype "passive"))
      (node (ref "R45") (pin "2") (pinfunction "2_2") (pintype "passive"))
    )
    (net (code "64") (name "Net-(Q10-E)") (class "Default")
      (node (ref "Q10") (pin "3") (pinfunction "E_3") (pintype "passive"))
      (node (ref "R44") (pin "2") (pinfunction "2_2") (pintype "passive"))
    )
    (net (code "65") (name "Net-(Q11-B)") (class "Default")
      (node (ref "C33") (pin "2") (pinfunction "2_2") (pintype "passive"))
      (node (ref "C34") (pin "1") (pinfunction "1_1") (pintype "passive"))
      (node (ref "Q11") (pin "1") (pinfunction "B_1") (pintype "passive"))
      (node (ref "R56") (pin "1") (pinfunction "1_1") (pintype "passive"))
      (node (ref "R57") (pin "2") (pinfunction "2_2") (pintype "passive"))
    )
    (net (code "66") (name "Net-(Q11-C)") (class "Default")
      (node (ref "C32") (pin "2") (pinfunction "2_2") (pintype "passive"))
      (node (ref "Q11") (pin "2") (pinfunction "C_2") (pintype "passive"))
      (node (ref "R55") (pin "1") (pinfunction "1_1") (pintype "passive"))
      (node (ref "R58") (pin "1") (pinfunction "1_1") (pintype "passive"))
      (node (ref "R61") (pin "1") (pinfunction "1_1") (pintype "passive"))
    )
    (net (code "67") (name "Net-(Q12-B)") (class "Default")
      (node (ref "C32") (pin "1") (pinfunction "1_1") (pintype "passive"))
      (node (ref "C35") (pin "1") (pinfunction "1_1") (pintype "passive"))
      (node (ref "Q12") (pin "1") (pinfunction "B_1") (pintype "passive"))
      (node (ref "R55") (pin "2") (pinfunction "2_2") (pintype "passive"))
      (node (ref "R60") (pin "2") (pinfunction "2_2") (pintype "passive"))
    )
    (net (code "68") (name "Net-(R10-Pad2)") (class "Default")
      (node (ref "R10") (pin "2") (pinfunction "2_2") (pintype "passive"))
      (node (ref "VR1") (pin "1") (pinfunction "1_1") (pintype "passive"))
    )
    (net (code "69") (name "Net-(R45-Pad1)") (class "Default")
      (node (ref "R45") (pin "1") (pinfunction "1_1") (pintype "passive"))
      (node (ref "VR2") (pin "2") (pinfunction "2_2") (pintype "passive"))
    )
    (net (code "70") (name "Net-(R52-Pad1)") (class "Default")
      (node (ref "R52") (pin "1") (pinfunction "1_1") (pintype "passive"))
      (node (ref "VR1") (pin "2") (pinfunction "2_2") (pintype "passive"))
    )
    (net (code "71") (name "Net-(SW1-O)") (class "Default")
      (node (ref "D2") (pin "C") (pinfunction "C_C") (pintype "passive"))
      (node (ref "D5") (pin "C") (pinfunction "C_C") (pintype "passive"))
      (node (ref "D7") (pin "C") (pinfunction "C_C") (pintype "passive"))
      (node (ref "R11") (pin "1") (pinfunction "1_1") (pintype "passive"))
      (node (ref "SW1") (pin "1") (pinfunction "O_1") (pintype "passive"))
    )
    (net (code "72") (name "Net-(SW1-P)") (class "Default")
      (node (ref "C9") (pin "1") (pinfunction "1_1") (pintype "passive"))
      (node (ref "R12") (pin "2") (pinfunction "2_2") (pintype "passive"))
      (node (ref "SW1") (pin "2") (pinfunction "P_2") (pintype "passive"))
    )
    (net (code "73") (name "Net-(SW2-S)") (class "Default")
      (node (ref "R63") (pin "1") (pinfunction "1_1") (pintype "passive"))
      (node (ref "SW2") (pin "2") (pinfunction "S_2") (pintype "passive"))
    )
    (net (code "74") (name "OUT") (class "Default")
      (node (ref "C7") (pin "-") (pinfunction "-_-") (pintype "passive"))
      (node (ref "C8") (pin "-") (pinfunction "-_-") (pintype "passive"))
      (node (ref "R5") (pin "2") (pinfunction "2_2") (pintype "passive"))
      (node (ref "R9") (pin "2") (pinfunction "2_2") (pintype "passive"))
    )
    (net (code "75") (name "VA") (class "Default")
      (node (ref "IC3") (pin "5") (pinfunction "5_5") (pintype "bidirectional"))
      (node (ref "IC4") (pin "1") (pinfunction "P$1_1") (pintype "bidirectional"))
      (node (ref "Q10") (pin "2") (pinfunction "C_2") (pintype "passive"))
      (node (ref "Q7") (pin "3") (pinfunction "E_3") (pintype "passive"))
      (node (ref "R40") (pin "2") (pinfunction "2_2") (pintype "passive"))
      (node (ref "R42") (pin "2") (pinfunction "2_2") (pintype "passive"))
      (node (ref "R46") (pin "2") (pinfunction "2_2") (pintype "passive"))
    )
    (net (code "76") (name "VB") (class "Default")
      (node (ref "C20") (pin "+") (pinfunction "+_+") (pintype "passive"))
      (node (ref "IC1") (pin "3") (pinfunction "+IN_3") (pintype "input"))
      (node (ref "IC2") (pin "3") (pinfunction "+IN_3") (pintype "input"))
      (node (ref "IC2") (pin "5") (pinfunction "+IN_5") (pintype "input"))
      (node (ref "R14") (pin "1") (pinfunction "1_1") (pintype "passive"))
      (node (ref "R16") (pin "1") (pinfunction "1_1") (pintype "passive"))
      (node (ref "R30") (pin "1") (pinfunction "1_1") (pintype "passive"))
      (node (ref "R35") (pin "1") (pinfunction "1_1") (pintype "passive"))
      (node (ref "R4") (pin "1") (pinfunction "1_1") (pintype "passive"))
      (node (ref "R54") (pin "2") (pinfunction "2_2") (pintype "passive"))
      (node (ref "R64") (pin "1") (pinfunction "1_1") (pintype "passive"))
    )
    (net (code "77") (name "VC") (class "Default")
      (node (ref "C27") (pin "+") (pinfunction "+_+") (pintype "passive"))
      (node (ref "IC5") (pin "5") (pinfunction "+IN_5") (pintype "input"))
      (node (ref "R10") (pin "1") (pinfunction "1_1") (pintype "passive"))
      (node (ref "R46") (pin "1") (pinfunction "1_1") (pintype "passive"))
      (node (ref "R50") (pin "2") (pinfunction "2_2") (pintype "passive"))
      (node (ref "R51") (pin "1") (pinfunction "1_1") (pintype "passive"))
      (node (ref "VR2") (pin "1") (pinfunction "1_1") (pintype "passive"))
    )
    (net (code "78") (name "unconnected-(IC4-P$6-Pad6)") (class "Default")
      (node (ref "IC4") (pin "6") (pinfunction "P$6_6") (pintype "bidirectional"))
    )
    (net (code "79") (name "unconnected-(SW1-S-Pad3)") (class "Default")
      (node (ref "SW1") (pin "3") (pinfunction "S_3") (pintype "passive"))
    )
  )
)
